# 07_Wireless.net
KiCad netlist of a schematic drawn in Altium Designer
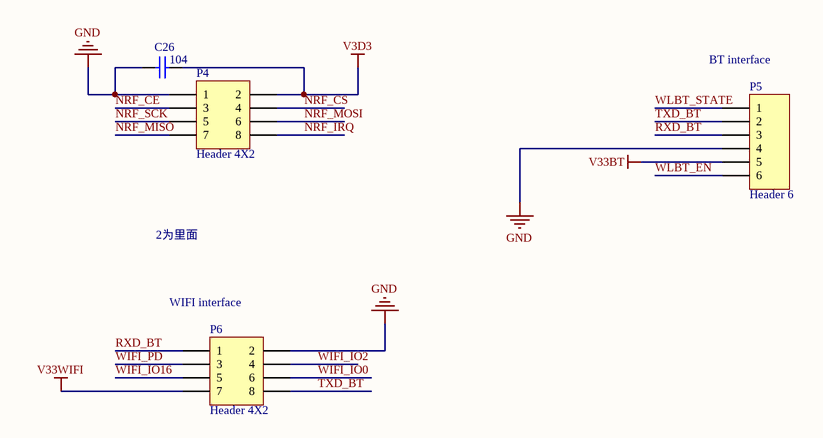
[diagram p0: 07_Wireless.SchDoc]

(export (version "E")
  (design (tool "Eeschema 10.0.6"))
  (components
    (comp (ref "C26")
      (value "104")
      (footprint "0402")
      (description "Capacitor")
      (fields (field (name "Comment") "Cap") (field (name "PUBLISHER") "Altium Limited"))
      (libsource (lib "Miscellaneous Devices") (part "Cap"))
    )
    (comp (ref "P4")
      (value "Header 4X2")
      (footprint "HDR2X4")
      (description "Header, 4-Pin, Dual row")
      (fields (field (name "PUBLISHER") "Altium Limited"))
      (libsource (lib "Miscellaneous Connectors") (part "Header 4X2"))
    )
    (comp (ref "P5")
      (value "Header 6")
      (footprint "HDR1X6")
      (description "Header, 6-Pin")
      (fields (field (name "PUBLISHER") "Altium Limited"))
      (libsource (lib "Miscellaneous Connectors") (part "Header 6"))
    )
    (comp (ref "P6")
      (value "Header 4X2")
      (footprint "HDR2X4")
      (description "Header, 4-Pin, Dual row")
      (fields (field (name "PUBLISHER") "Altium Limited"))
      (libsource (lib "Miscellaneous Connectors") (part "Header 4X2"))
    )
  )
  (nets
    (net (code "1") (name "/NRF_CE") (class "Default")
      (node (ref "P4") (pin "3") (pinfunction "3_3") (pintype "passive"))
    )
    (net (code "2") (name "/NRF_CS") (class "Default")
      (node (ref "P4") (pin "4") (pinfunction "4_4") (pintype "passive"))
    )
    (net (code "3") (name "/NRF_IRQ") (class "Default")
      (node (ref "P4") (pin "8") (pinfunction "8_8") (pintype "passive"))
    )
    (net (code "4") (name "/NRF_MISO") (class "Default")
      (node (ref "P4") (pin "7") (pinfunction "7_7") (pintype "passive"))
    )
    (net (code "5") (name "/NRF_MOSI") (class "Default")
      (node (ref "P4") (pin "6") (pinfunction "6_6") (pintype "passive"))
    )
    (net (code "6") (name "/NRF_SCK") (class "Default")
      (node (ref "P4") (pin "5") (pinfunction "5_5") (pintype "passive"))
    )
    (net (code "7") (name "/RXD_BT") (class "Default")
      (node (ref "P5") (pin "3") (pinfunction "3_3") (pintype "passive"))
      (node (ref "P6") (pin "1") (pinfunction "1_1") (pintype "passive"))
    )
    (net (code "8") (name "/TXD_BT") (class "Default")
      (node (ref "P5") (pin "2") (pinfunction "2_2") (pintype "passive"))
      (node (ref "P6") (pin "8") (pinfunction "8_8") (pintype "passive"))
    )
    (net (code "9") (name "/WIFI_IO0") (class "Default")
      (node (ref "P6") (pin "6") (pinfunction "6_6") (pintype "passive"))
    )
    (net (code "10") (name "/WIFI_IO2") (class "Default")
      (node (ref "P6") (pin "4") (pinfunction "4_4") (pintype "passive"))
    )
    (net (code "11") (name "/WIFI_IO16") (class "Default")
      (node (ref "P6") (pin "5") (pinfunction "5_5") (pintype "passive"))
    )
    (net (code "12") (name "/WIFI_PD") (class "Default")
      (node (ref "P6") (pin "3") (pinfunction "3_3") (pintype "passive"))
    )
    (net (code "13") (name "/WLBT_EN") (class "Default")
      (node (ref "P5") (pin "6") (pinfunction "6_6") (pintype "passive"))
    )
    (net (code "14") (name "/WLBT_STATE") (class "Default")
      (node (ref "P5") (pin "1") (pinfunction "1_1") (pintype "passive"))
    )
    (net (code "15") (name "GND") (class "Default")
      (node (ref "C26") (pin "1") (pinfunction "1_1") (pintype "passive"))
      (node (ref "P4") (pin "1") (pinfunction "1_1") (pintype "passive"))
      (node (ref "P5") (pin "4") (pinfunction "4_4") (pintype "passive"))
      (node (ref "P6") (pin "2") (pinfunction "2_2") (pintype "passive"))
    )
    (net (code "16") (name "V3D3") (class "Default")
      (node (ref "C26") (pin "2") (pinfunction "2_2") (pintype "passive"))
      (node (ref "P4") (pin "2") (pinfunction "2_2") (pintype "passive"))
    )
    (net (code "17") (name "V33BT") (class "Default")
      (node (ref "P5") (pin "5") (pinfunction "5_5") (pintype "passive"))
    )
    (net (code "18") (name "V33WIFI") (class "Default")
      (node (ref "P6") (pin "7") (pinfunction "7_7") (pintype "passive"))
    )
  )
)
